# Schematic.net
KiCad netlist of a schematic drawn in Altium Designer
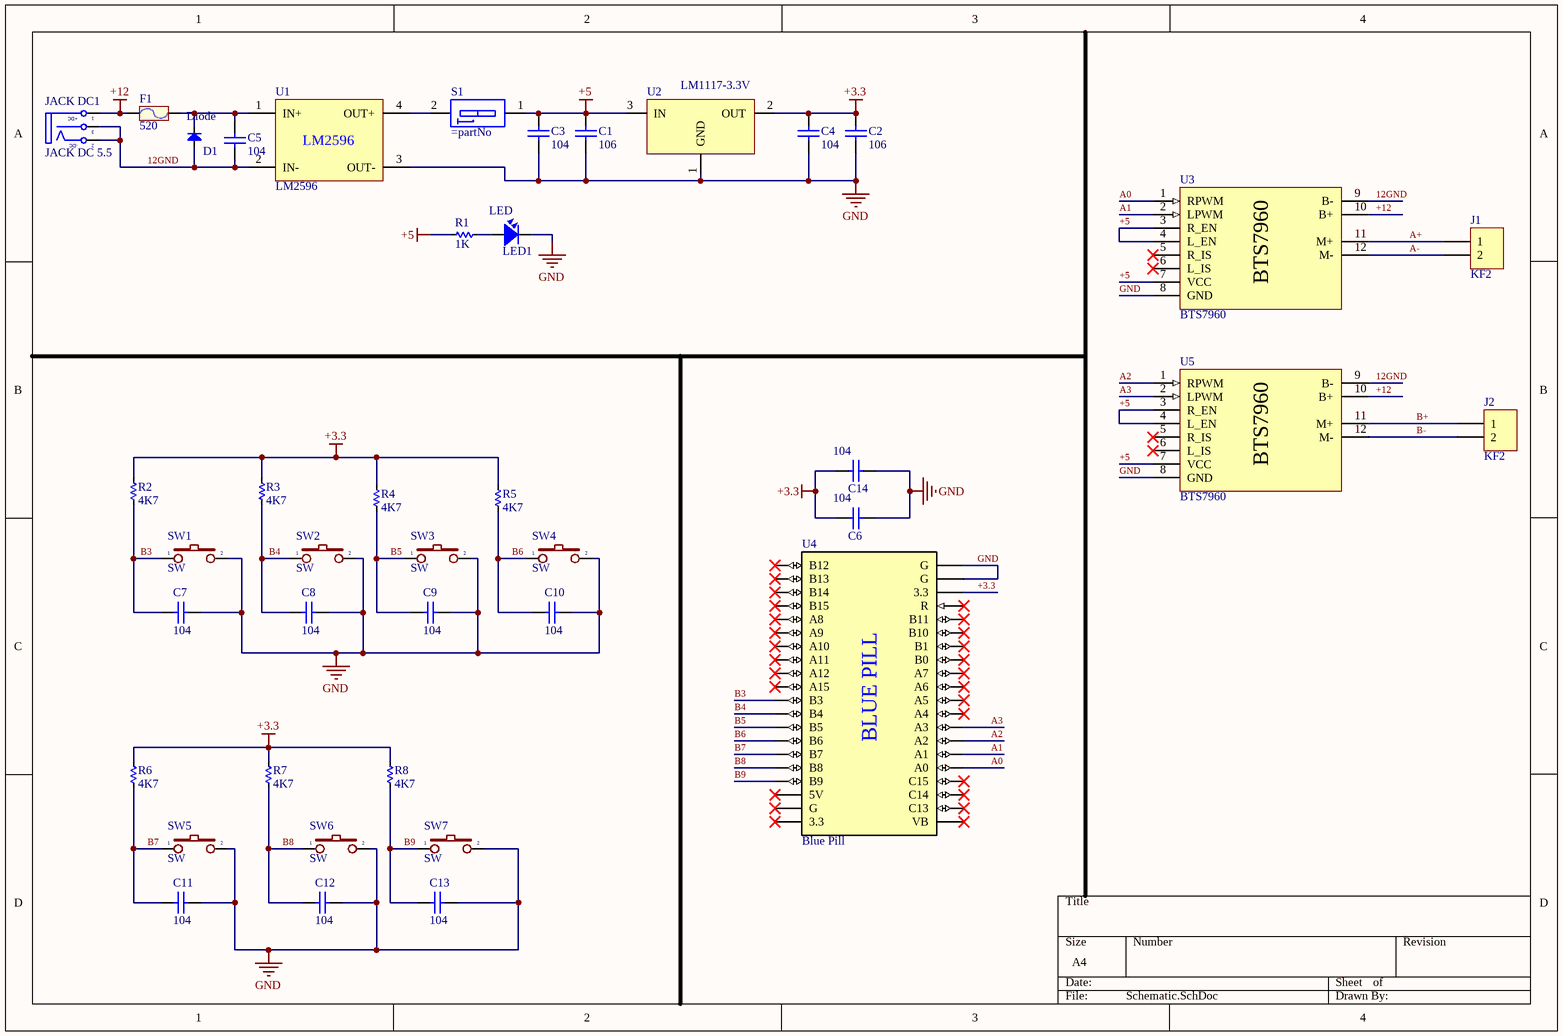
[diagram p0: Schematic.SchDoc]

(export (version "E")
  (design (tool "Eeschema 10.0.6"))
  (components
    (comp (ref "C1")
      (value "106")
      (footprint "tu gom")
      (description "Cắm")
      (libsource (lib "Altium_Lib_by_KhueNguyenCreator") (part "Tu gom 104 50V"))
    )
    (comp (ref "C2")
      (value "106")
      (footprint "tu gom")
      (description "Cắm")
      (libsource (lib "Altium_Lib_by_KhueNguyenCreator") (part "Tu gom 104 50V"))
    )
    (comp (ref "C3")
      (value "104")
      (footprint "tu gom")
      (description "Cắm")
      (libsource (lib "Altium_Lib_by_KhueNguyenCreator") (part "Tu gom 104 50V"))
    )
    (comp (ref "C4")
      (value "104")
      (footprint "tu gom")
      (description "Cắm")
      (libsource (lib "Altium_Lib_by_KhueNguyenCreator") (part "Tu gom 104 50V"))
    )
    (comp (ref "C5")
      (value "104")
      (footprint "tu gom")
      (description "Cắm")
      (libsource (lib "Altium_Lib_by_KhueNguyenCreator") (part "Tu gom 104 50V"))
    )
    (comp (ref "C6")
      (value "104")
      (footprint "tu gom")
      (description "Cắm")
      (libsource (lib "Altium_Lib_by_KhueNguyenCreator") (part "Tu gom 104 50V"))
    )
    (comp (ref "C7")
      (value "104")
      (footprint "tu gom")
      (description "Cắm")
      (libsource (lib "Altium_Lib_by_KhueNguyenCreator") (part "Tu gom 104 50V"))
    )
    (comp (ref "C8")
      (value "104")
      (footprint "tu gom")
      (description "Cắm")
      (libsource (lib "Altium_Lib_by_KhueNguyenCreator") (part "Tu gom 104 50V"))
    )
    (comp (ref "C9")
      (value "104")
      (footprint "tu gom")
      (description "Cắm")
      (libsource (lib "Altium_Lib_by_KhueNguyenCreator") (part "Tu gom 104 50V"))
    )
    (comp (ref "C10")
      (value "104")
      (footprint "tu gom")
      (description "Cắm")
      (libsource (lib "Altium_Lib_by_KhueNguyenCreator") (part "Tu gom 104 50V"))
    )
    (comp (ref "C11")
      (value "104")
      (footprint "tu gom")
      (description "Cắm")
      (libsource (lib "Altium_Lib_by_KhueNguyenCreator") (part "Tu gom 104 50V"))
    )
    (comp (ref "C12")
      (value "104")
      (footprint "tu gom")
      (description "Cắm")
      (libsource (lib "Altium_Lib_by_KhueNguyenCreator") (part "Tu gom 104 50V"))
    )
    (comp (ref "C13")
      (value "104")
      (footprint "tu gom")
      (description "Cắm")
      (libsource (lib "Altium_Lib_by_KhueNguyenCreator") (part "Tu gom 104 50V"))
    )
    (comp (ref "C14")
      (value "104")
      (footprint "tu gom")
      (description "Cắm")
      (libsource (lib "Altium_Lib_by_KhueNguyenCreator") (part "Tu gom 104 50V"))
    )
    (comp (ref "D1")
      (value "Diode")
      (footprint "DIO-1A-SMALL")
      (description "Default Diode")
      (fields (field (name "PUBLISHER") "Altium Limited"))
      (libsource (lib "LIBRARY") (part "Diode"))
    )
    (comp (ref "F1")
      (value "520")
      (footprint "De Cau Chi 520 630")
      (description "5x20mm")
      (libsource (lib "Altium_Lib_by_KhueNguyenCreator") (part "De Cau Chi 520 630"))
    )
    (comp (ref "J1")
      (value "KF2")
      (footprint "KF2-5.08")
      (fields
        (field (name "MANUFACTURER") "Würth Elektronik eiSos GmbH")
        (field (name "PARTNO") "691103110002")
        (field (name "CREATED BY") "Karrer Zheng")
      )
      (libsource (lib "TechMT.VN_Lib_Project v2") (part "KF2"))
    )
    (comp (ref "J2")
      (value "KF2")
      (footprint "KF2-5.08")
      (fields
        (field (name "MANUFACTURER") "Würth Elektronik eiSos GmbH")
        (field (name "PARTNO") "691103110002")
        (field (name "CREATED BY") "Karrer Zheng")
      )
      (libsource (lib "TechMT.VN_Lib_Project v2") (part "KF2"))
    )
    (comp (ref "JACK DC1")
      (value "JACK DC 5.5")
      (footprint "JACK DC 5.5")
      (libsource (lib "Altium_Lib_by_KhueNguyenCreator") (part "JACK DC 5.5"))
    )
    (comp (ref "LED1")
      (value "LED")
      (footprint "LED-3MM-YELLOW")
      (description "LED Single colour Green and Red")
      (libsource (lib "TechMT.VN_Lib_Project v2") (part "LED"))
    )
    (comp (ref "R1")
      (value "1K")
      (footprint "RES-1/4W")
      (description "Res")
      (fields
        (field (name "MANUFACTURER") "Generic Components")
        (field (name "PUBLISHER") "Altium Hobart Technology Centre")
      )
      (libsource (lib "TechMT.VN_Lib_Project v2") (part "Res"))
    )
    (comp (ref "R2")
      (value "4K7")
      (footprint "RES-1/4W")
      (description "Res")
      (fields
        (field (name "MANUFACTURER") "Generic Components")
        (field (name "PUBLISHER") "Altium Hobart Technology Centre")
      )
      (libsource (lib "TechMT.VN_Lib_Project v2") (part "Res"))
    )
    (comp (ref "R3")
      (value "4K7")
      (footprint "RES-1/4W")
      (description "Res")
      (fields
        (field (name "MANUFACTURER") "Generic Components")
        (field (name "PUBLISHER") "Altium Hobart Technology Centre")
      )
      (libsource (lib "TechMT.VN_Lib_Project v2") (part "Res"))
    )
    (comp (ref "R4")
      (value "4K7")
      (footprint "RES-1/4W")
      (description "Res")
      (fields
        (field (name "MANUFACTURER") "Generic Components")
        (field (name "PUBLISHER") "Altium Hobart Technology Centre")
      )
      (libsource (lib "TechMT.VN_Lib_Project v2") (part "Res"))
    )
    (comp (ref "R5")
      (value "4K7")
      (footprint "RES-1/4W")
      (description "Res")
      (fields
        (field (name "MANUFACTURER") "Generic Components")
        (field (name "PUBLISHER") "Altium Hobart Technology Centre")
      )
      (libsource (lib "TechMT.VN_Lib_Project v2") (part "Res"))
    )
    (comp (ref "R6")
      (value "4K7")
      (footprint "RES-1/4W")
      (description "Res")
      (fields
        (field (name "MANUFACTURER") "Generic Components")
        (field (name "PUBLISHER") "Altium Hobart Technology Centre")
      )
      (libsource (lib "TechMT.VN_Lib_Project v2") (part "Res"))
    )
    (comp (ref "R7")
      (value "4K7")
      (footprint "RES-1/4W")
      (description "Res")
      (fields
        (field (name "MANUFACTURER") "Generic Components")
        (field (name "PUBLISHER") "Altium Hobart Technology Centre")
      )
      (libsource (lib "TechMT.VN_Lib_Project v2") (part "Res"))
    )
    (comp (ref "R8")
      (value "4K7")
      (footprint "RES-1/4W")
      (description "Res")
      (fields
        (field (name "MANUFACTURER") "Generic Components")
        (field (name "PUBLISHER") "Altium Hobart Technology Centre")
      )
      (libsource (lib "TechMT.VN_Lib_Project v2") (part "Res"))
    )
    (comp (ref "S1")
      (value "~")
      (footprint "SW-DIP1")
      (description "WS-DITV 2.54 mm small compact THT flat actuator with top tape")
      (fields
        (field (name "MANUFACTURER") "Wurth Elektronik")
        (field (name "PART NO.") "418127160901")
        (field (name "CREATED BY") "Baojun Chen")
      )
      (libsource (lib "LIBRARY") (part "SWDIP1"))
    )
    (comp (ref "SW1")
      (value "SW")
      (footprint "SW2")
      (description "Switch button 2 pin")
      (libsource (lib "syhaunguyen") (part "SW2"))
    )
    (comp (ref "SW2")
      (value "SW")
      (footprint "SW2")
      (description "Switch button 2 pin")
      (libsource (lib "syhaunguyen") (part "SW2"))
    )
    (comp (ref "SW3")
      (value "SW")
      (footprint "SW2")
      (description "Switch button 2 pin")
      (libsource (lib "syhaunguyen") (part "SW2"))
    )
    (comp (ref "SW4")
      (value "SW")
      (footprint "SW2")
      (description "Switch button 2 pin")
      (libsource (lib "syhaunguyen") (part "SW2"))
    )
    (comp (ref "SW5")
      (value "SW")
      (footprint "SW2")
      (description "Switch button 2 pin")
      (libsource (lib "syhaunguyen") (part "SW2"))
    )
    (comp (ref "SW6")
      (value "SW")
      (footprint "SW2")
      (description "Switch button 2 pin")
      (libsource (lib "syhaunguyen") (part "SW2"))
    )
    (comp (ref "SW7")
      (value "SW")
      (footprint "SW2")
      (description "Switch button 2 pin")
      (libsource (lib "syhaunguyen") (part "SW2"))
    )
    (comp (ref "U1")
      (value "LM2596")
      (footprint "AZ_Lib:LM2596 Module")
      (description "DC - DC Buck")
      (libsource (lib "AZ_Lib") (part "LM2596 Module"))
    )
    (comp (ref "U2")
      (value "LM1117-3.3V")
      (footprint "TO220-123")
      (description "800mA Low-Dropout Linear Regulator")
      (fields (field (name "CREATOR") "Nguyen Ba Bien"))
      (libsource (lib "TechMT.VN_Lib_Project v2") (part "LM1117"))
    )
    (comp (ref "U3")
      (value "BTS7960")
      (footprint "BTS7960 Module")
      (description "Driver BTS Module")
      (libsource (lib "AZ_Lib") (part "BTS7960 Module"))
    )
    (comp (ref "U4")
      (value "Blue Pill")
      (footprint "AZ_Lib:Blue Pill STM32F103")
      (description "Blue Pill STM32F103C8T6")
      (libsource (lib "AZ_Lib") (part "Blue Pill STM32F103"))
    )
    (comp (ref "U5")
      (value "BTS7960")
      (footprint "BTS7960 Module")
      (description "Driver BTS Module")
      (libsource (lib "AZ_Lib") (part "BTS7960 Module"))
    )
  )
  (nets
    (net (code "1") (name "+3.3") (class "Default")
      (node (ref "C14") (pin "1") (pinfunction "1_1") (pintype "passive"))
      (node (ref "C2") (pin "1") (pinfunction "1_1") (pintype "passive"))
      (node (ref "C4") (pin "1") (pinfunction "1_1") (pintype "passive"))
      (node (ref "C6") (pin "1") (pinfunction "1_1") (pintype "passive"))
      (node (ref "R2") (pin "1") (pinfunction "1_1") (pintype "passive"))
      (node (ref "R3") (pin "1") (pinfunction "1_1") (pintype "passive"))
      (node (ref "R4") (pin "1") (pinfunction "1_1") (pintype "passive"))
      (node (ref "R5") (pin "1") (pinfunction "1_1") (pintype "passive"))
      (node (ref "R6") (pin "1") (pinfunction "1_1") (pintype "passive"))
      (node (ref "R7") (pin "1") (pinfunction "1_1") (pintype "passive"))
      (node (ref "R8") (pin "1") (pinfunction "1_1") (pintype "passive"))
      (node (ref "U2") (pin "2") (pinfunction "OUT_2") (pintype "passive"))
      (node (ref "U4") (pin "38") (pinfunction "3.3_38") (pintype "power_in"))
    )
    (net (code "2") (name "+5") (class "Default")
      (node (ref "C1") (pin "1") (pinfunction "1_1") (pintype "passive"))
      (node (ref "C3") (pin "1") (pinfunction "1_1") (pintype "passive"))
      (node (ref "R1") (pin "2") (pinfunction "2_2") (pintype "passive"))
      (node (ref "S1") (pin "1") (pinfunction "1_1") (pintype "passive"))
      (node (ref "U2") (pin "3") (pinfunction "IN_3") (pintype "passive"))
      (node (ref "U3") (pin "3") (pinfunction "R_EN_3") (pintype "passive"))
      (node (ref "U3") (pin "4") (pinfunction "L_EN_4") (pintype "passive"))
      (node (ref "U3") (pin "7") (pinfunction "VCC_7") (pintype "power_in"))
      (node (ref "U5") (pin "3") (pinfunction "R_EN_3") (pintype "passive"))
      (node (ref "U5") (pin "4") (pinfunction "L_EN_4") (pintype "passive"))
      (node (ref "U5") (pin "7") (pinfunction "VCC_7") (pintype "power_in"))
    )
    (net (code "3") (name "+12") (class "Default")
      (node (ref "F1") (pin "1") (pinfunction "1_1") (pintype "passive"))
      (node (ref "JACK DC1") (pin "1") (pinfunction "T_1") (pintype "passive"))
      (node (ref "U3") (pin "10") (pinfunction "B+_10") (pintype "power_in"))
      (node (ref "U5") (pin "10") (pinfunction "B+_10") (pintype "power_in"))
    )
    (net (code "4") (name "/12GND") (class "Default")
      (node (ref "C5") (pin "2") (pinfunction "2_2") (pintype "passive"))
      (node (ref "D1") (pin "1") (pinfunction "A_1") (pintype "passive"))
      (node (ref "JACK DC1") (pin "2") (pinfunction "TN_2") (pintype "passive"))
      (node (ref "JACK DC1") (pin "3") (pinfunction "S_3") (pintype "power_in"))
      (node (ref "U1") (pin "2") (pinfunction "IN-_2") (pintype "passive"))
      (node (ref "U3") (pin "9") (pinfunction "B-_9") (pintype "power_in"))
      (node (ref "U5") (pin "9") (pinfunction "B-_9") (pintype "power_in"))
    )
    (net (code "5") (name "/A+") (class "Default")
      (node (ref "J1") (pin "1") (pinfunction "1_1") (pintype "passive"))
      (node (ref "U3") (pin "11") (pinfunction "M+_11") (pintype "passive"))
    )
    (net (code "6") (name "/A-") (class "Default")
      (node (ref "J1") (pin "2") (pinfunction "2_2") (pintype "passive"))
      (node (ref "U3") (pin "12") (pinfunction "M-_12") (pintype "passive"))
    )
    (net (code "7") (name "/A0") (class "Default")
      (node (ref "U3") (pin "1") (pinfunction "RPWM_1") (pintype "input"))
      (node (ref "U4") (pin "25") (pinfunction "A0_25") (pintype "bidirectional"))
    )
    (net (code "8") (name "/A1") (class "Default")
      (node (ref "U3") (pin "2") (pinfunction "LPWM_2") (pintype "input"))
      (node (ref "U4") (pin "26") (pinfunction "A1_26") (pintype "bidirectional"))
    )
    (net (code "9") (name "/A2") (class "Default")
      (node (ref "U4") (pin "27") (pinfunction "A2_27") (pintype "bidirectional"))
      (node (ref "U5") (pin "1") (pinfunction "RPWM_1") (pintype "input"))
    )
    (net (code "10") (name "/A3") (class "Default")
      (node (ref "U4") (pin "28") (pinfunction "A3_28") (pintype "bidirectional"))
      (node (ref "U5") (pin "2") (pinfunction "LPWM_2") (pintype "input"))
    )
    (net (code "11") (name "/B+") (class "Default")
      (node (ref "J2") (pin "1") (pinfunction "1_1") (pintype "passive"))
      (node (ref "U5") (pin "11") (pinfunction "M+_11") (pintype "passive"))
    )
    (net (code "12") (name "/B-") (class "Default")
      (node (ref "J2") (pin "2") (pinfunction "2_2") (pintype "passive"))
      (node (ref "U5") (pin "12") (pinfunction "M-_12") (pintype "passive"))
    )
    (net (code "13") (name "/B3") (class "Default")
      (node (ref "C7") (pin "1") (pinfunction "1_1") (pintype "passive"))
      (node (ref "R2") (pin "2") (pinfunction "2_2") (pintype "passive"))
      (node (ref "SW1") (pin "1") (pinfunction "1_1") (pintype "passive"))
      (node (ref "U4") (pin "11") (pinfunction "B3_11") (pintype "bidirectional"))
    )
    (net (code "14") (name "/B4") (class "Default")
      (node (ref "C8") (pin "1") (pinfunction "1_1") (pintype "passive"))
      (node (ref "R3") (pin "2") (pinfunction "2_2") (pintype "passive"))
      (node (ref "SW2") (pin "1") (pinfunction "1_1") (pintype "passive"))
      (node (ref "U4") (pin "12") (pinfunction "B4_12") (pintype "bidirectional"))
    )
    (net (code "15") (name "/B5") (class "Default")
      (node (ref "C9") (pin "1") (pinfunction "1_1") (pintype "passive"))
      (node (ref "R4") (pin "2") (pinfunction "2_2") (pintype "passive"))
      (node (ref "SW3") (pin "1") (pinfunction "1_1") (pintype "passive"))
      (node (ref "U4") (pin "13") (pinfunction "B5_13") (pintype "bidirectional"))
    )
    (net (code "16") (name "/B6") (class "Default")
      (node (ref "C10") (pin "1") (pinfunction "1_1") (pintype "passive"))
      (node (ref "R5") (pin "2") (pinfunction "2_2") (pintype "passive"))
      (node (ref "SW4") (pin "1") (pinfunction "1_1") (pintype "passive"))
      (node (ref "U4") (pin "14") (pinfunction "B6_14") (pintype "bidirectional"))
    )
    (net (code "17") (name "/B7") (class "Default")
      (node (ref "C11") (pin "1") (pinfunction "1_1") (pintype "passive"))
      (node (ref "R6") (pin "2") (pinfunction "2_2") (pintype "passive"))
      (node (ref "SW5") (pin "1") (pinfunction "1_1") (pintype "passive"))
      (node (ref "U4") (pin "15") (pinfunction "B7_15") (pintype "bidirectional"))
    )
    (net (code "18") (name "/B8") (class "Default")
      (node (ref "C12") (pin "1") (pinfunction "1_1") (pintype "passive"))
      (node (ref "R7") (pin "2") (pinfunction "2_2") (pintype "passive"))
      (node (ref "SW6") (pin "1") (pinfunction "1_1") (pintype "passive"))
      (node (ref "U4") (pin "16") (pinfunction "B8_16") (pintype "bidirectional"))
    )
    (net (code "19") (name "/B9") (class "Default")
      (node (ref "C13") (pin "1") (pinfunction "1_1") (pintype "passive"))
      (node (ref "R8") (pin "2") (pinfunction "2_2") (pintype "passive"))
      (node (ref "SW7") (pin "1") (pinfunction "1_1") (pintype "passive"))
      (node (ref "U4") (pin "17") (pinfunction "B9_17") (pintype "bidirectional"))
    )
    (net (code "20") (name "GND") (class "Default")
      (node (ref "C1") (pin "2") (pinfunction "2_2") (pintype "passive"))
      (node (ref "C10") (pin "2") (pinfunction "2_2") (pintype "passive"))
      (node (ref "C11") (pin "2") (pinfunction "2_2") (pintype "passive"))
      (node (ref "C12") (pin "2") (pinfunction "2_2") (pintype "passive"))
      (node (ref "C13") (pin "2") (pinfunction "2_2") (pintype "passive"))
      (node (ref "C14") (pin "2") (pinfunction "2_2") (pintype "passive"))
      (node (ref "C2") (pin "2") (pinfunction "2_2") (pintype "passive"))
      (node (ref "C3") (pin "2") (pinfunction "2_2") (pintype "passive"))
      (node (ref "C4") (pin "2") (pinfunction "2_2") (pintype "passive"))
      (node (ref "C6") (pin "2") (pinfunction "2_2") (pintype "passive"))
      (node (ref "C7") (pin "2") (pinfunction "2_2") (pintype "passive"))
      (node (ref "C8") (pin "2") (pinfunction "2_2") (pintype "passive"))
      (node (ref "C9") (pin "2") (pinfunction "2_2") (pintype "passive"))
      (node (ref "LED1") (pin "2") (pinfunction "2_2") (pintype "passive"))
      (node (ref "SW1") (pin "2") (pinfunction "2_2") (pintype "passive"))
      (node (ref "SW2") (pin "2") (pinfunction "2_2") (pintype "passive"))
      (node (ref "SW3") (pin "2") (pinfunction "2_2") (pintype "passive"))
      (node (ref "SW4") (pin "2") (pinfunction "2_2") (pintype "passive"))
      (node (ref "SW5") (pin "2") (pinfunction "2_2") (pintype "passive"))
      (node (ref "SW6") (pin "2") (pinfunction "2_2") (pintype "passive"))
      (node (ref "SW7") (pin "2") (pinfunction "2_2") (pintype "passive"))
      (node (ref "U1") (pin "3") (pinfunction "OUT-_3") (pintype "passive"))
      (node (ref "U2") (pin "1") (pinfunction "GND_1") (pintype "passive"))
      (node (ref "U3") (pin "8") (pinfunction "GND_8") (pintype "power_in"))
      (node (ref "U4") (pin "39") (pinfunction "G_39") (pintype "power_in"))
      (node (ref "U4") (pin "40") (pinfunction "G_40") (pintype "power_in"))
      (node (ref "U5") (pin "8") (pinfunction "GND_8") (pintype "power_in"))
    )
    (net (code "21") (name "Net-(D1-K)") (class "Default")
      (node (ref "C5") (pin "1") (pinfunction "1_1") (pintype "passive"))
      (node (ref "D1") (pin "2") (pinfunction "K_2") (pintype "passive"))
      (node (ref "F1") (pin "2") (pinfunction "2_2") (pintype "passive"))
      (node (ref "U1") (pin "1") (pinfunction "IN+_1") (pintype "passive"))
    )
    (net (code "22") (name "Net-(LED1-Pad1)") (class "Default")
      (node (ref "LED1") (pin "1") (pinfunction "1_1") (pintype "passive"))
      (node (ref "R1") (pin "1") (pinfunction "1_1") (pintype "passive"))
    )
    (net (code "23") (name "Net-(U1-OUT+)") (class "Default")
      (node (ref "S1") (pin "2") (pinfunction "2_2") (pintype "passive"))
      (node (ref "U1") (pin "4") (pinfunction "OUT+_4") (pintype "passive"))
    )
    (net (code "24") (name "unconnected-(U3-L_IS-Pad6)") (class "Default")
      (node (ref "U3") (pin "6") (pinfunction "L_IS_6") (pintype "passive+no_connect"))
    )
    (net (code "25") (name "unconnected-(U3-R_IS-Pad5)") (class "Default")
      (node (ref "U3") (pin "5") (pinfunction "R_IS_5") (pintype "passive+no_connect"))
    )
    (net (code "26") (name "unconnected-(U4-3.3-Pad20)") (class "Default")
      (node (ref "U4") (pin "20") (pinfunction "3.3_20") (pintype "power_in+no_connect"))
    )
    (net (code "27") (name "unconnected-(U4-5V-Pad18)") (class "Default")
      (node (ref "U4") (pin "18") (pinfunction "5V_18") (pintype "power_in+no_connect"))
    )
    (net (code "28") (name "unconnected-(U4-A4-Pad29)") (class "Default")
      (node (ref "U4") (pin "29") (pinfunction "A4_29") (pintype "bidirectional+no_connect"))
    )
    (net (code "29") (name "unconnected-(U4-A5-Pad30)") (class "Default")
      (node (ref "U4") (pin "30") (pinfunction "A5_30") (pintype "bidirectional+no_connect"))
    )
    (net (code "30") (name "unconnected-(U4-A6-Pad31)") (class "Default")
      (node (ref "U4") (pin "31") (pinfunction "A6_31") (pintype "bidirectional+no_connect"))
    )
    (net (code "31") (name "unconnected-(U4-A7-Pad32)") (class "Default")
      (node (ref "U4") (pin "32") (pinfunction "A7_32") (pintype "bidirectional+no_connect"))
    )
    (net (code "32") (name "unconnected-(U4-A8-Pad5)") (class "Default")
      (node (ref "U4") (pin "5") (pinfunction "A8_5") (pintype "bidirectional+no_connect"))
    )
    (net (code "33") (name "unconnected-(U4-A9-Pad6)") (class "Default")
      (node (ref "U4") (pin "6") (pinfunction "A9_6") (pintype "bidirectional+no_connect"))
    )
    (net (code "34") (name "unconnected-(U4-A10-Pad7)") (class "Default")
      (node (ref "U4") (pin "7") (pinfunction "A10_7") (pintype "bidirectional+no_connect"))
    )
    (net (code "35") (name "unconnected-(U4-A11-Pad8)") (class "Default")
      (node (ref "U4") (pin "8") (pinfunction "A11_8") (pintype "bidirectional+no_connect"))
    )
    (net (code "36") (name "unconnected-(U4-A12-Pad9)") (class "Default")
      (node (ref "U4") (pin "9") (pinfunction "A12_9") (pintype "bidirectional+no_connect"))
    )
    (net (code "37") (name "unconnected-(U4-A15-Pad10)") (class "Default")
      (node (ref "U4") (pin "10") (pinfunction "A15_10") (pintype "bidirectional+no_connect"))
    )
    (net (code "38") (name "unconnected-(U4-B0-Pad33)") (class "Default")
      (node (ref "U4") (pin "33") (pinfunction "B0_33") (pintype "bidirectional+no_connect"))
    )
    (net (code "39") (name "unconnected-(U4-B1-Pad34)") (class "Default")
      (node (ref "U4") (pin "34") (pinfunction "B1_34") (pintype "bidirectional+no_connect"))
    )
    (net (code "40") (name "unconnected-(U4-B10-Pad35)") (class "Default")
      (node (ref "U4") (pin "35") (pinfunction "B10_35") (pintype "bidirectional+no_connect"))
    )
    (net (code "41") (name "unconnected-(U4-B11-Pad36)") (class "Default")
      (node (ref "U4") (pin "36") (pinfunction "B11_36") (pintype "bidirectional+no_connect"))
    )
    (net (code "42") (name "unconnected-(U4-B12-Pad1)") (class "Default")
      (node (ref "U4") (pin "1") (pinfunction "B12_1") (pintype "bidirectional+no_connect"))
    )
    (net (code "43") (name "unconnected-(U4-B13-Pad2)") (class "Default")
      (node (ref "U4") (pin "2") (pinfunction "B13_2") (pintype "bidirectional+no_connect"))
    )
    (net (code "44") (name "unconnected-(U4-B14-Pad3)") (class "Default")
      (node (ref "U4") (pin "3") (pinfunction "B14_3") (pintype "bidirectional+no_connect"))
    )
    (net (code "45") (name "unconnected-(U4-B15-Pad4)") (class "Default")
      (node (ref "U4") (pin "4") (pinfunction "B15_4") (pintype "bidirectional+no_connect"))
    )
    (net (code "46") (name "unconnected-(U4-C13-Pad22)") (class "Default")
      (node (ref "U4") (pin "22") (pinfunction "C13_22") (pintype "bidirectional+no_connect"))
    )
    (net (code "47") (name "unconnected-(U4-C14-Pad23)") (class "Default")
      (node (ref "U4") (pin "23") (pinfunction "C14_23") (pintype "bidirectional+no_connect"))
    )
    (net (code "48") (name "unconnected-(U4-C15-Pad24)") (class "Default")
      (node (ref "U4") (pin "24") (pinfunction "C15_24") (pintype "bidirectional+no_connect"))
    )
    (net (code "49") (name "unconnected-(U4-G-Pad19)") (class "Default")
      (node (ref "U4") (pin "19") (pinfunction "G_19") (pintype "power_in+no_connect"))
    )
    (net (code "50") (name "unconnected-(U4-R-Pad37)") (class "Default")
      (node (ref "U4") (pin "37") (pinfunction "R_37") (pintype "input+no_connect"))
    )
    (net (code "51") (name "unconnected-(U4-VB-Pad21)") (class "Default")
      (node (ref "U4") (pin "21") (pinfunction "VB_21") (pintype "power_in+no_connect"))
    )
    (net (code "52") (name "unconnected-(U5-L_IS-Pad6)") (class "Default")
      (node (ref "U5") (pin "6") (pinfunction "L_IS_6") (pintype "passive+no_connect"))
    )
    (net (code "53") (name "unconnected-(U5-R_IS-Pad5)") (class "Default")
      (node (ref "U5") (pin "5") (pinfunction "R_IS_5") (pintype "passive+no_connect"))
    )
  )
)
